# Base_plate.net
KiCad netlist of a schematic drawn in Altium Designer
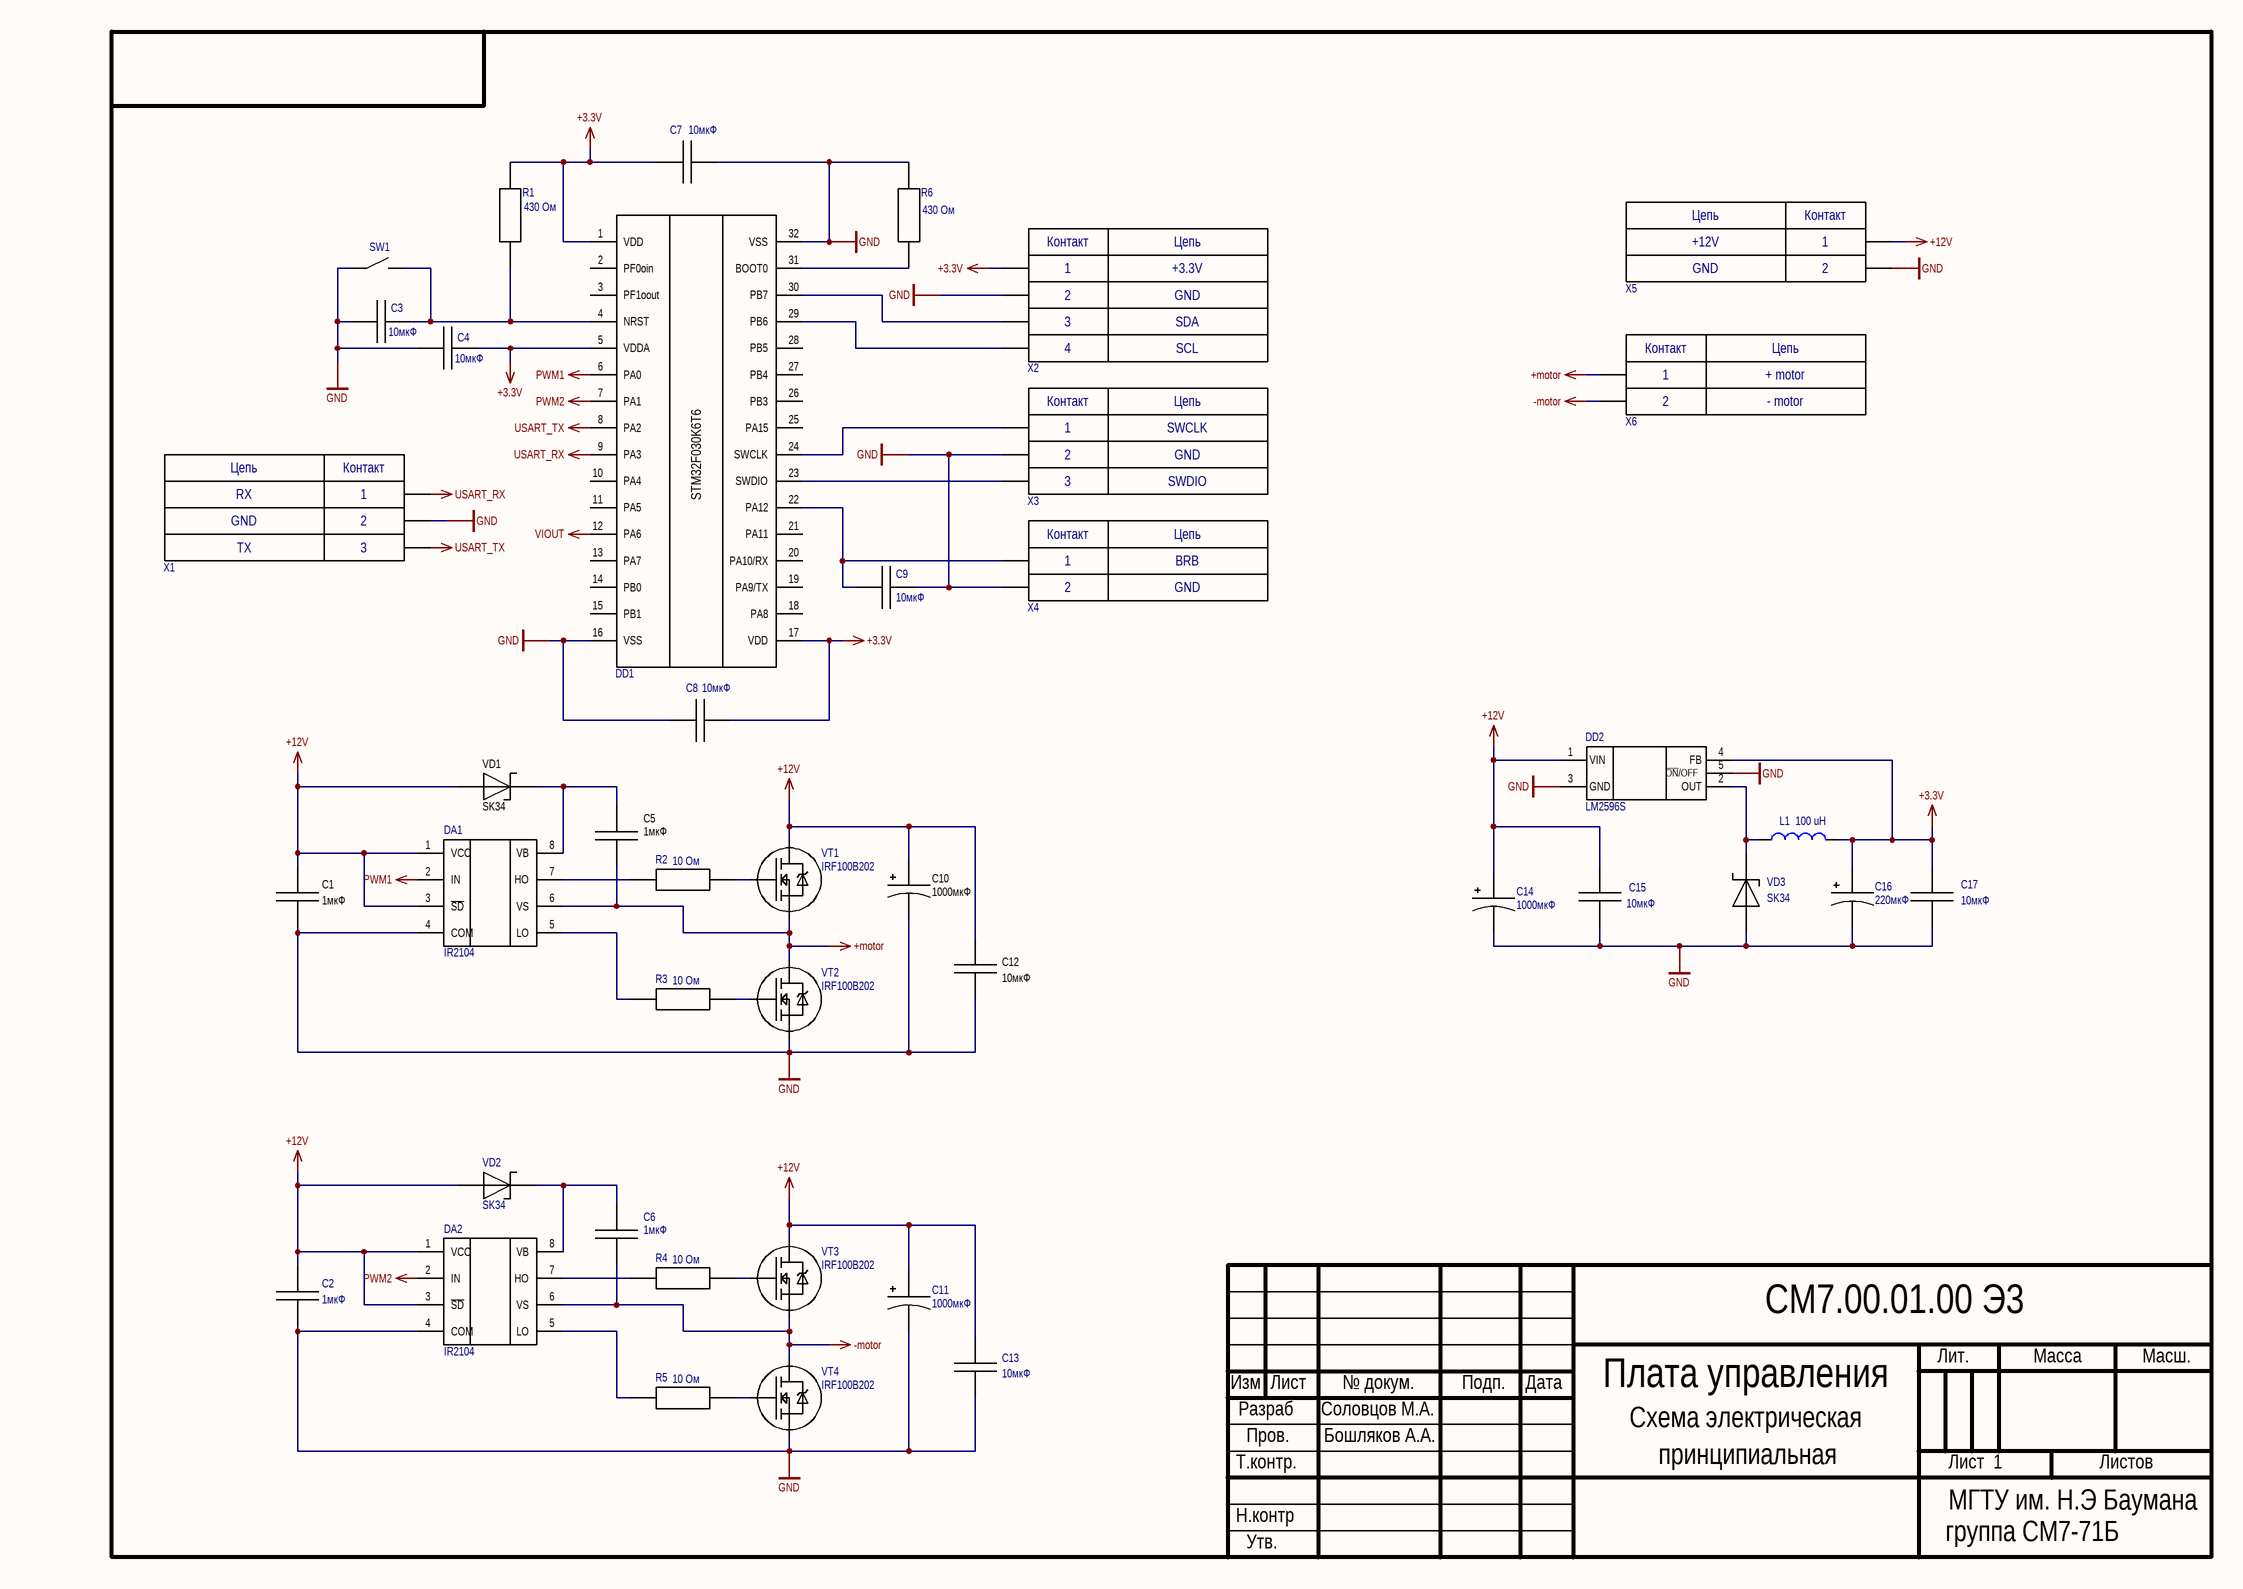
[diagram p0: Base_plate.SchDoc]

(export (version "E")
  (design (tool "Eeschema 10.0.6"))
  (components
    (comp (ref "C1")
      (value "1мкФ")
      (footprint "CAP 10 uF")
      (description "GRM21BR71H105K")
      (libsource (lib "Schlib1") (part "Capacitor 0805"))
    )
    (comp (ref "C2")
      (value "1мкФ")
      (footprint "CAP 10 uF")
      (description "GRM21BR71H105K")
      (libsource (lib "Schlib1") (part "Capacitor 0805"))
    )
    (comp (ref "C3")
      (value "10мкФ")
      (footprint "CAP 10 uF")
      (description "0805X106K350SNT")
      (libsource (lib "Schlib1") (part "Capacitor 0805"))
    )
    (comp (ref "C4")
      (value "10мкФ")
      (footprint "CAP 10 uF")
      (description "0805X106K350SNT")
      (libsource (lib "Schlib1") (part "Capacitor 0805"))
    )
    (comp (ref "C5")
      (value "1мкФ")
      (footprint "CAP 10 uF")
      (description "GRM21BR71H105K")
      (libsource (lib "Schlib1") (part "Capacitor 0805"))
    )
    (comp (ref "C6")
      (value "1мкФ")
      (footprint "CAP 10 uF")
      (description "GRM21BR71H105K")
      (libsource (lib "Schlib1") (part "Capacitor 0805"))
    )
    (comp (ref "C7")
      (value "10мкФ")
      (footprint "CAP 10 uF")
      (description "0805X106K350SNT")
      (libsource (lib "Schlib1") (part "Capacitor 0805"))
    )
    (comp (ref "C8")
      (value "10мкФ")
      (footprint "CAP 10 uF")
      (description "0805X106K350SNT")
      (libsource (lib "Schlib1") (part "Capacitor 0805"))
    )
    (comp (ref "C9")
      (value "10мкФ")
      (footprint "CAP 10 uF")
      (description "0805X106K350SNT")
      (libsource (lib "Schlib1") (part "Capacitor 0805"))
    )
    (comp (ref "C10")
      (value "1000мкФ")
      (footprint "cap 1000")
      (libsource (lib "Schlib2") (part "Capacitor  El"))
    )
    (comp (ref "C11")
      (value "1000мкФ")
      (footprint "cap 1000")
      (libsource (lib "Schlib2") (part "Capacitor  El"))
    )
    (comp (ref "C12")
      (value "10мкФ")
      (footprint "CAP 10 uF")
      (description "0805X106K350SNT")
      (libsource (lib "Schlib1") (part "Capacitor 0805"))
    )
    (comp (ref "C13")
      (value "10мкФ")
      (footprint "CAP 10 uF")
      (description "0805X106K350SNT")
      (libsource (lib "Schlib1") (part "Capacitor 0805"))
    )
    (comp (ref "C14")
      (value "1000мкФ")
      (footprint "cap 1000")
      (libsource (lib "Schlib2") (part "Capacitor  El"))
    )
    (comp (ref "C15")
      (value "10мкФ")
      (footprint "CAP 10 uF")
      (description "0805X106K350SNT")
      (libsource (lib "Schlib1") (part "Capacitor 0805"))
    )
    (comp (ref "C16")
      (value "220мкФ")
      (footprint "Capacitor 220nF E")
      (libsource (lib "Schlib2") (part "CAPACIATOR E D6.3"))
    )
    (comp (ref "C17")
      (value "10мкФ")
      (footprint "CAP 10 uF")
      (description "0805X106K350SNT")
      (libsource (lib "Schlib1") (part "Capacitor 0805"))
    )
    (comp (ref "DA1") (value "IR2104") (footprint "IR2104") (libsource (lib "Schlib2") (part "IR2104")))
    (comp (ref "DA2") (value "IR2104") (footprint "IR2104") (libsource (lib "Schlib2") (part "IR2104")))
    (comp (ref "DD1")
      (value "STM32F030K6T6")
      (footprint "QFP32(7x7)")
      (libsource (lib "Schlib2") (part "STM32F030K6T6"))
    )
    (comp (ref "DD2") (value "LM2596S") (footprint "LM2596") (libsource (lib "Schlib2") (part "LM2596S")))
    (comp (ref "L1")
      (value "100 uH")
      (footprint "INDUCTOR")
      (description "Inductor")
      (fields (field (name "PUBLISHER") "Altium Limited"))
      (libsource (lib "Miscellaneous Devices") (part "Inductor"))
    )
    (comp (ref "R1")
      (value "430 Ом")
      (footprint "0402")
      (fields (field (name "Comment") "430R"))
      (libsource (lib "Schlib2") (part "Resistor"))
    )
    (comp (ref "R2")
      (value "10 Ом")
      (footprint "0402")
      (fields (field (name "Comment") "Resistor"))
      (libsource (lib "Schlib2") (part "Resistor"))
    )
    (comp (ref "R3")
      (value "10 Ом")
      (footprint "0402")
      (fields (field (name "Comment") "Resistor"))
      (libsource (lib "Schlib2") (part "Resistor"))
    )
    (comp (ref "R4")
      (value "10 Ом")
      (footprint "0402")
      (fields (field (name "Comment") "Resistor"))
      (libsource (lib "Schlib2") (part "Resistor"))
    )
    (comp (ref "R5")
      (value "10 Ом")
      (footprint "0402")
      (fields (field (name "Comment") "Resistor"))
      (libsource (lib "Schlib2") (part "Resistor"))
    )
    (comp (ref "R6")
      (value "430 Ом")
      (footprint "0402")
      (fields (field (name "Comment") "430R"))
      (libsource (lib "Schlib2") (part "Resistor"))
    )
    (comp (ref "SW1") (value "Button") (footprint "button") (libsource (lib "ButtonsLib") (part "Button")))
    (comp (ref "VD1") (value "SK34") (footprint "SK34") (libsource (lib "Schlib1") (part "SK34")))
    (comp (ref "VD2") (value "SK34") (footprint "SK34") (libsource (lib "Schlib1") (part "SK34")))
    (comp (ref "VD3") (value "SK34") (footprint "SK34") (libsource (lib "Schlib1") (part "SK34")))
    (comp (ref "VT1")
      (value "IRF100B202")
      (footprint "TO-220AB")
      (description "N-Channel 55V 110A _Tc_ 200W _Tc_ Through Hole TO-220AB")
      (fields (field (name "MP") "IRF3205PBF") (field (name "MF") "Infineon Technologies"))
      (libsource (lib "Schlib2") (part "IRF3205PBF"))
    )
    (comp (ref "VT2")
      (value "IRF100B202")
      (footprint "TO-220AB")
      (description "N-Channel 55V 110A _Tc_ 200W _Tc_ Through Hole TO-220AB")
      (fields (field (name "MP") "IRF3205PBF") (field (name "MF") "Infineon Technologies"))
      (libsource (lib "Schlib2") (part "IRF3205PBF"))
    )
    (comp (ref "VT3")
      (value "IRF100B202")
      (footprint "TO-220AB")
      (description "N-Channel 55V 110A _Tc_ 200W _Tc_ Through Hole TO-220AB")
      (fields (field (name "MP") "IRF3205PBF") (field (name "MF") "Infineon Technologies"))
      (libsource (lib "Schlib2") (part "IRF3205PBF"))
    )
    (comp (ref "VT4")
      (value "IRF100B202")
      (footprint "TO-220AB")
      (description "N-Channel 55V 110A _Tc_ 200W _Tc_ Through Hole TO-220AB")
      (fields (field (name "MP") "IRF3205PBF") (field (name "MF") "Infineon Technologies"))
      (libsource (lib "Schlib2") (part "IRF3205PBF"))
    )
    (comp (ref "X1") (value "3pin") (footprint "3pin") (libsource (lib "Schlib2") (part "3pin")))
    (comp (ref "X2") (value "4pin") (footprint "4pin") (libsource (lib "Schlib2") (part "4pin_1")))
    (comp (ref "X3") (value "3pin") (footprint "3pin") (libsource (lib "Schlib2") (part "3pin")))
    (comp (ref "X4") (value "2pin") (footprint "2pin5mmVintKlemm") (libsource (lib "Schlib2") (part "2pin")))
    (comp (ref "X5") (value "2pin") (footprint "2pin5mmVintKlemm") (libsource (lib "Schlib2") (part "2pin")))
    (comp (ref "X6") (value "2pin") (footprint "2pin5mmVintKlemm") (libsource (lib "Schlib2") (part "2pin")))
  )
  (nets
    (net (code "1") (name "+3.3V") (class "Default")
      (node (ref "C16") (pin "1") (pinfunction "3_1") (pintype "passive"))
      (node (ref "C17") (pin "1") (pinfunction "1_1") (pintype "passive"))
      (node (ref "C4") (pin "2") (pinfunction "2_2") (pintype "passive"))
      (node (ref "C7") (pin "1") (pinfunction "1_1") (pintype "passive"))
      (node (ref "C8") (pin "2") (pinfunction "2_2") (pintype "passive"))
      (node (ref "DD1") (pin "1") (pinfunction "VDD_1") (pintype "passive"))
      (node (ref "DD1") (pin "17") (pinfunction "VDD_17") (pintype "passive"))
      (node (ref "DD1") (pin "5") (pinfunction "VDDA_5") (pintype "passive"))
      (node (ref "DD2") (pin "4") (pinfunction "FB_4") (pintype "passive"))
      (node (ref "L1") (pin "2") (pinfunction "2_2") (pintype "passive"))
      (node (ref "R1") (pin "2") (pinfunction "2_2") (pintype "passive"))
      (node (ref "X2") (pin "1") (pinfunction "1_1") (pintype "passive"))
    )
    (net (code "2") (name "+12V") (class "Default")
      (node (ref "C1") (pin "2") (pinfunction "2_2") (pintype "passive"))
      (node (ref "C10") (pin "1") (pinfunction "3_1") (pintype "passive"))
      (node (ref "C11") (pin "1") (pinfunction "3_1") (pintype "passive"))
      (node (ref "C12") (pin "1") (pinfunction "1_1") (pintype "passive"))
      (node (ref "C13") (pin "1") (pinfunction "1_1") (pintype "passive"))
      (node (ref "C14") (pin "1") (pinfunction "3_1") (pintype "passive"))
      (node (ref "C15") (pin "1") (pinfunction "1_1") (pintype "passive"))
      (node (ref "C2") (pin "2") (pinfunction "2_2") (pintype "passive"))
      (node (ref "DA1") (pin "1") (pinfunction "VCC_1") (pintype "passive"))
      (node (ref "DA1") (pin "3") (pinfunction "SD_3") (pintype "passive"))
      (node (ref "DA2") (pin "1") (pinfunction "VCC_1") (pintype "passive"))
      (node (ref "DA2") (pin "3") (pinfunction "SD_3") (pintype "passive"))
      (node (ref "DD2") (pin "1") (pinfunction "VIN_1") (pintype "passive"))
      (node (ref "VD1") (pin "1") (pinfunction "1_1") (pintype "passive"))
      (node (ref "VD2") (pin "1") (pinfunction "1_1") (pintype "passive"))
      (node (ref "VT1") (pin "2") (pinfunction "6_2") (pintype "passive"))
      (node (ref "VT3") (pin "2") (pinfunction "6_2") (pintype "passive"))
      (node (ref "X5") (pin "1") (pinfunction "1_1") (pintype "passive"))
    )
    (net (code "3") (name "+motor") (class "Default")
      (node (ref "C5") (pin "1") (pinfunction "1_1") (pintype "passive"))
      (node (ref "DA1") (pin "6") (pinfunction "VS_6") (pintype "passive"))
      (node (ref "VT1") (pin "3") (pinfunction "7_3") (pintype "passive"))
      (node (ref "VT2") (pin "2") (pinfunction "6_2") (pintype "passive"))
      (node (ref "X6") (pin "1") (pinfunction "1_1") (pintype "passive"))
    )
    (net (code "4") (name "-motor") (class "Default")
      (node (ref "C6") (pin "1") (pinfunction "1_1") (pintype "passive"))
      (node (ref "DA2") (pin "6") (pinfunction "VS_6") (pintype "passive"))
      (node (ref "VT3") (pin "3") (pinfunction "7_3") (pintype "passive"))
      (node (ref "VT4") (pin "2") (pinfunction "6_2") (pintype "passive"))
      (node (ref "X6") (pin "2") (pinfunction "-Vout_2") (pintype "passive"))
    )
    (net (code "5") (name "GND") (class "Default")
      (node (ref "C1") (pin "1") (pinfunction "1_1") (pintype "passive"))
      (node (ref "C10") (pin "2") (pinfunction "4_2") (pintype "passive"))
      (node (ref "C11") (pin "2") (pinfunction "4_2") (pintype "passive"))
      (node (ref "C12") (pin "2") (pinfunction "2_2") (pintype "passive"))
      (node (ref "C13") (pin "2") (pinfunction "2_2") (pintype "passive"))
      (node (ref "C14") (pin "2") (pinfunction "4_2") (pintype "passive"))
      (node (ref "C15") (pin "2") (pinfunction "2_2") (pintype "passive"))
      (node (ref "C16") (pin "2") (pinfunction "3_2") (pintype "passive"))
      (node (ref "C17") (pin "2") (pinfunction "2_2") (pintype "passive"))
      (node (ref "C2") (pin "1") (pinfunction "1_1") (pintype "passive"))
      (node (ref "C3") (pin "1") (pinfunction "1_1") (pintype "passive"))
      (node (ref "C4") (pin "1") (pinfunction "1_1") (pintype "passive"))
      (node (ref "C7") (pin "2") (pinfunction "2_2") (pintype "passive"))
      (node (ref "C8") (pin "1") (pinfunction "1_1") (pintype "passive"))
      (node (ref "C9") (pin "2") (pinfunction "2_2") (pintype "passive"))
      (node (ref "DA1") (pin "4") (pinfunction "COM_4") (pintype "passive"))
      (node (ref "DA2") (pin "4") (pinfunction "COM_4") (pintype "passive"))
      (node (ref "DD1") (pin "16") (pinfunction "VSS_16") (pintype "passive"))
      (node (ref "DD1") (pin "32") (pinfunction "VSS_32") (pintype "passive"))
      (node (ref "DD2") (pin "3") (pinfunction "GND_3") (pintype "passive"))
      (node (ref "DD2") (pin "5") (pinfunction "~{ON}/OFF_5") (pintype "passive"))
      (node (ref "R6") (pin "2") (pinfunction "2_2") (pintype "passive"))
      (node (ref "SW1") (pin "1") (pinfunction "G_1") (pintype "passive"))
      (node (ref "VD3") (pin "1") (pinfunction "1_1") (pintype "passive"))
      (node (ref "VT2") (pin "3") (pinfunction "7_3") (pintype "passive"))
      (node (ref "VT4") (pin "3") (pinfunction "7_3") (pintype "passive"))
      (node (ref "X1") (pin "2") (pinfunction "-Vout_2") (pintype "passive"))
      (node (ref "X2") (pin "2") (pinfunction "-Vout_2") (pintype "passive"))
      (node (ref "X3") (pin "2") (pinfunction "-Vout_2") (pintype "passive"))
      (node (ref "X4") (pin "2") (pinfunction "-Vout_2") (pintype "passive"))
      (node (ref "X5") (pin "2") (pinfunction "-Vout_2") (pintype "passive"))
    )
    (net (code "6") (name "Net-(DA1-HO)") (class "Default")
      (node (ref "DA1") (pin "7") (pinfunction "HO_7") (pintype "passive"))
      (node (ref "R2") (pin "1") (pinfunction "1_1") (pintype "passive"))
    )
    (net (code "7") (name "Net-(DA1-LO)") (class "Default")
      (node (ref "DA1") (pin "5") (pinfunction "LO_5") (pintype "passive"))
      (node (ref "R3") (pin "1") (pinfunction "1_1") (pintype "passive"))
    )
    (net (code "8") (name "Net-(DA1-VB)") (class "Default")
      (node (ref "C5") (pin "2") (pinfunction "2_2") (pintype "passive"))
      (node (ref "DA1") (pin "8") (pinfunction "VB_8") (pintype "passive"))
      (node (ref "VD1") (pin "2") (pinfunction "2_2") (pintype "passive"))
    )
    (net (code "9") (name "Net-(DA2-HO)") (class "Default")
      (node (ref "DA2") (pin "7") (pinfunction "HO_7") (pintype "passive"))
      (node (ref "R4") (pin "1") (pinfunction "1_1") (pintype "passive"))
    )
    (net (code "10") (name "Net-(DA2-LO)") (class "Default")
      (node (ref "DA2") (pin "5") (pinfunction "LO_5") (pintype "passive"))
      (node (ref "R5") (pin "1") (pinfunction "1_1") (pintype "passive"))
    )
    (net (code "11") (name "Net-(DA2-VB)") (class "Default")
      (node (ref "C6") (pin "2") (pinfunction "2_2") (pintype "passive"))
      (node (ref "DA2") (pin "8") (pinfunction "VB_8") (pintype "passive"))
      (node (ref "VD2") (pin "2") (pinfunction "2_2") (pintype "passive"))
    )
    (net (code "12") (name "Net-(DD1-BOOT0)") (class "Default")
      (node (ref "DD1") (pin "31") (pinfunction "BOOT0_31") (pintype "passive"))
      (node (ref "R6") (pin "1") (pinfunction "1_1") (pintype "passive"))
    )
    (net (code "13") (name "Net-(DD1-NRST)") (class "Default")
      (node (ref "C3") (pin "2") (pinfunction "2_2") (pintype "passive"))
      (node (ref "DD1") (pin "4") (pinfunction "NRST_4") (pintype "passive"))
      (node (ref "R1") (pin "1") (pinfunction "1_1") (pintype "passive"))
      (node (ref "SW1") (pin "2") (pinfunction "G_2") (pintype "passive"))
    )
    (net (code "14") (name "Net-(DD1-PA12)") (class "Default")
      (node (ref "C9") (pin "1") (pinfunction "1_1") (pintype "passive"))
      (node (ref "DD1") (pin "22") (pinfunction "PA12_22") (pintype "passive"))
      (node (ref "X4") (pin "1") (pinfunction "1_1") (pintype "passive"))
    )
    (net (code "15") (name "Net-(DD1-PB6)") (class "Default")
      (node (ref "DD1") (pin "29") (pinfunction "PB6_29") (pintype "passive"))
      (node (ref "X2") (pin "4") (pinfunction "-Vout_4") (pintype "passive"))
    )
    (net (code "16") (name "Net-(DD1-PB7)") (class "Default")
      (node (ref "DD1") (pin "30") (pinfunction "PB7_30") (pintype "passive"))
      (node (ref "X2") (pin "3") (pinfunction "-Vout_3") (pintype "passive"))
    )
    (net (code "17") (name "Net-(DD1-SWCLK)") (class "Default")
      (node (ref "DD1") (pin "24") (pinfunction "SWCLK_24") (pintype "passive"))
      (node (ref "X3") (pin "1") (pinfunction "1_1") (pintype "passive"))
    )
    (net (code "18") (name "Net-(DD1-SWDIO)") (class "Default")
      (node (ref "DD1") (pin "23") (pinfunction "SWDIO_23") (pintype "passive"))
      (node (ref "X3") (pin "3") (pinfunction "-Vout_3") (pintype "passive"))
    )
    (net (code "19") (name "Net-(DD2-OUT)") (class "Default")
      (node (ref "DD2") (pin "2") (pinfunction "OUT_2") (pintype "passive"))
      (node (ref "L1") (pin "1") (pinfunction "1_1") (pintype "passive"))
      (node (ref "VD3") (pin "2") (pinfunction "2_2") (pintype "passive"))
    )
    (net (code "20") (name "Net-(VT1-5)") (class "Default")
      (node (ref "R2") (pin "2") (pinfunction "2_2") (pintype "passive"))
      (node (ref "VT1") (pin "1") (pinfunction "5_1") (pintype "passive"))
    )
    (net (code "21") (name "Net-(VT2-5)") (class "Default")
      (node (ref "R3") (pin "2") (pinfunction "2_2") (pintype "passive"))
      (node (ref "VT2") (pin "1") (pinfunction "5_1") (pintype "passive"))
    )
    (net (code "22") (name "Net-(VT3-5)") (class "Default")
      (node (ref "R4") (pin "2") (pinfunction "2_2") (pintype "passive"))
      (node (ref "VT3") (pin "1") (pinfunction "5_1") (pintype "passive"))
    )
    (net (code "23") (name "Net-(VT4-5)") (class "Default")
      (node (ref "R5") (pin "2") (pinfunction "2_2") (pintype "passive"))
      (node (ref "VT4") (pin "1") (pinfunction "5_1") (pintype "passive"))
    )
    (net (code "24") (name "PWM1") (class "Default")
      (node (ref "DA1") (pin "2") (pinfunction "IN_2") (pintype "passive"))
      (node (ref "DD1") (pin "6") (pinfunction "PA0_6") (pintype "passive"))
    )
    (net (code "25") (name "PWM2") (class "Default")
      (node (ref "DA2") (pin "2") (pinfunction "IN_2") (pintype "passive"))
      (node (ref "DD1") (pin "7") (pinfunction "PA1_7") (pintype "passive"))
    )
    (net (code "26") (name "USART_RX") (class "Default")
      (node (ref "DD1") (pin "9") (pinfunction "PA3_9") (pintype "passive"))
      (node (ref "X1") (pin "1") (pinfunction "1_1") (pintype "passive"))
    )
    (net (code "27") (name "USART_TX") (class "Default")
      (node (ref "DD1") (pin "8") (pinfunction "PA2_8") (pintype "passive"))
      (node (ref "X1") (pin "3") (pinfunction "-Vout_3") (pintype "passive"))
    )
    (net (code "28") (name "VIOUT") (class "Default")
      (node (ref "DD1") (pin "12") (pinfunction "PA6_12") (pintype "passive"))
    )
    (net (code "29") (name "unconnected-(DD1-PA4-Pad10)") (class "Default")
      (node (ref "DD1") (pin "10") (pinfunction "PA4_10") (pintype "passive"))
    )
    (net (code "30") (name "unconnected-(DD1-PA5-Pad11)") (class "Default")
      (node (ref "DD1") (pin "11") (pinfunction "PA5_11") (pintype "passive"))
    )
    (net (code "31") (name "unconnected-(DD1-PA7-Pad13)") (class "Default")
      (node (ref "DD1") (pin "13") (pinfunction "PA7_13") (pintype "passive"))
    )
    (net (code "32") (name "unconnected-(DD1-PA8-Pad18)") (class "Default")
      (node (ref "DD1") (pin "18") (pinfunction "PA8_18") (pintype "passive"))
    )
    (net (code "33") (name "unconnected-(DD1-PA9{slash}TX-Pad19)") (class "Default")
      (node (ref "DD1") (pin "19") (pinfunction "PA9/TX_19") (pintype "passive"))
    )
    (net (code "34") (name "unconnected-(DD1-PA10{slash}RX-Pad20)") (class "Default")
      (node (ref "DD1") (pin "20") (pinfunction "PA10/RX_20") (pintype "passive"))
    )
    (net (code "35") (name "unconnected-(DD1-PA11-Pad21)") (class "Default")
      (node (ref "DD1") (pin "21") (pinfunction "PA11_21") (pintype "passive"))
    )
    (net (code "36") (name "unconnected-(DD1-PA15-Pad25)") (class "Default")
      (node (ref "DD1") (pin "25") (pinfunction "PA15_25") (pintype "passive"))
    )
    (net (code "37") (name "unconnected-(DD1-PB0-Pad14)") (class "Default")
      (node (ref "DD1") (pin "14") (pinfunction "PB0_14") (pintype "passive"))
    )
    (net (code "38") (name "unconnected-(DD1-PB1-Pad15)") (class "Default")
      (node (ref "DD1") (pin "15") (pinfunction "PB1_15") (pintype "passive"))
    )
    (net (code "39") (name "unconnected-(DD1-PB3-Pad26)") (class "Default")
      (node (ref "DD1") (pin "26") (pinfunction "PB3_26") (pintype "passive"))
    )
    (net (code "40") (name "unconnected-(DD1-PB4-Pad27)") (class "Default")
      (node (ref "DD1") (pin "27") (pinfunction "PB4_27") (pintype "passive"))
    )
    (net (code "41") (name "unconnected-(DD1-PB5-Pad28)") (class "Default")
      (node (ref "DD1") (pin "28") (pinfunction "PB5_28") (pintype "passive"))
    )
    (net (code "42") (name "unconnected-(DD1-PF0oin-Pad2)") (class "Default")
      (node (ref "DD1") (pin "2") (pinfunction "PF0oin_2") (pintype "passive"))
    )
    (net (code "43") (name "unconnected-(DD1-PF1oout-Pad3)") (class "Default")
      (node (ref "DD1") (pin "3") (pinfunction "PF1oout_3") (pintype "passive"))
    )
  )
)
